# nrf51.net
KiCad netlist of a schematic drawn in Altium Designer
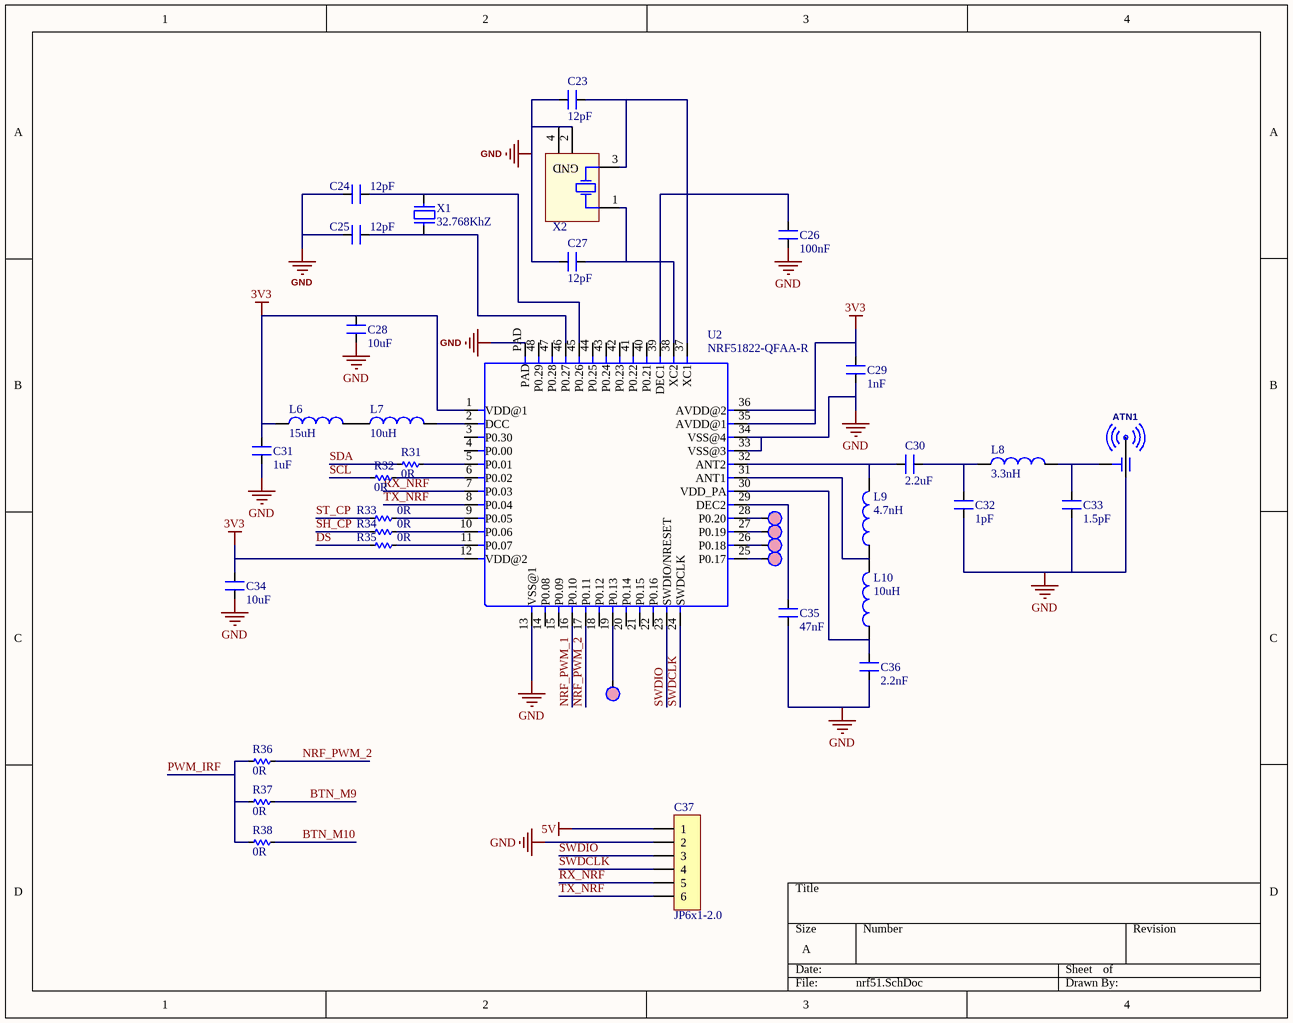
[diagram p0: nrf51.SchDoc]

(export (version "E")
  (design (tool "Eeschema 10.0.6"))
  (components
    (comp (ref "ATN1")
      (value "P-ANT")
      (footprint "Antenna 2G4")
      (libsource (lib "VitalSignal EcgPpg Board") (part "P-ANT"))
    )
    (comp (ref "C23")
      (value "12pF")
      (footprint "CN-SMD-0603")
      (description "Tu gom")
      (libsource (lib "LIBTanCN") (part "CN"))
    )
    (comp (ref "C24")
      (value "12pF")
      (footprint "CN-SMD-0603")
      (description "Tu gom")
      (libsource (lib "LIBTanCN") (part "CN"))
    )
    (comp (ref "C25")
      (value "12pF")
      (footprint "CN-SMD-0603")
      (description "Tu gom")
      (libsource (lib "LIBTanCN") (part "CN"))
    )
    (comp (ref "C26")
      (value "100nF")
      (footprint "CN-SMD-0603")
      (description "Tu gom")
      (libsource (lib "LIBTanCN") (part "CN"))
    )
    (comp (ref "C27")
      (value "12pF")
      (footprint "CN-SMD-0603")
      (description "Tu gom")
      (libsource (lib "LIBTanCN") (part "CN"))
    )
    (comp (ref "C28")
      (value "10uF")
      (footprint "CN-SMD-0603")
      (description "Tu gom")
      (libsource (lib "LIBTanCN") (part "CN"))
    )
    (comp (ref "C29")
      (value "1nF")
      (footprint "CN-SMD-0603")
      (description "Tu gom")
      (libsource (lib "LIBTanCN") (part "CN"))
    )
    (comp (ref "C30")
      (value "2.2uF")
      (footprint "CN-SMD-0603")
      (description "Tu gom")
      (libsource (lib "LIBTanCN") (part "CN"))
    )
    (comp (ref "C31")
      (value "1uF")
      (footprint "CN-SMD-0603")
      (description "Tu gom")
      (libsource (lib "LIBTanCN") (part "CN"))
    )
    (comp (ref "C32")
      (value "1pF")
      (footprint "CN-SMD-0603")
      (description "Tu gom")
      (libsource (lib "LIBTanCN") (part "CN"))
    )
    (comp (ref "C33")
      (value "1.5pF")
      (footprint "CN-SMD-0603")
      (description "Tu gom")
      (libsource (lib "LIBTanCN") (part "CN"))
    )
    (comp (ref "C34")
      (value "10uF")
      (footprint "CN-SMD-0603")
      (description "Tu gom")
      (libsource (lib "LIBTanCN") (part "CN"))
    )
    (comp (ref "C35")
      (value "47nF")
      (footprint "CN-SMD-0603")
      (description "Tu gom")
      (libsource (lib "LIBTanCN") (part "CN"))
    )
    (comp (ref "C36")
      (value "2.2nF")
      (footprint "CN-SMD-0603")
      (description "Tu gom")
      (libsource (lib "LIBTanCN") (part "CN"))
    )
    (comp (ref "C37")
      (value "JP6x1-2.0")
      (footprint "J6-C1T")
      (description "WR-PHD 2.00 mm Socket Header")
      (fields
        (field (name "MANUFACTURER") "Würth Elektronik eiSos GmbH")
        (field (name "PARTNO") "62000611821")
        (field (name "CREATED BY") "Karrer Zheng")
      )
      (libsource (lib "LIBRARY") (part "JP6x1-2.0"))
    )
    (comp (ref "L6")
      (value "15uH")
      (footprint "Inductor_0603:INDC1608X95N")
      (description "Ind Chip Shielded Multi-Layer 10uH 30% 1MHz Ferrite 50mA 0603 T/R")
      (fields (field (name "MP") "ASMCI-0603-100N-T"))
      (libsource (lib "Inductor_0603") (part "ASMCI-0603-100N-T"))
    )
    (comp (ref "L7")
      (value "10uH")
      (footprint "Inductor_0603:INDC1608X95N")
      (description "Ind Chip Shielded Multi-Layer 10uH 30% 1MHz Ferrite 50mA 0603 T/R")
      (fields (field (name "MP") "ASMCI-0603-100N-T"))
      (libsource (lib "Inductor_0603") (part "ASMCI-0603-100N-T"))
    )
    (comp (ref "L8")
      (value "3.3nH")
      (footprint "Inductor_0603:INDC1608X95N")
      (description "Ind Chip Shielded Multi-Layer 10uH 30% 1MHz Ferrite 50mA 0603 T/R")
      (fields (field (name "MP") "ASMCI-0603-100N-T"))
      (libsource (lib "Inductor_0603") (part "ASMCI-0603-100N-T"))
    )
    (comp (ref "L9")
      (value "4.7nH")
      (footprint "Inductor_0603:INDC1608X95N")
      (description "Ind Chip Shielded Multi-Layer 10uH 30% 1MHz Ferrite 50mA 0603 T/R")
      (fields (field (name "MP") "ASMCI-0603-100N-T"))
      (libsource (lib "Inductor_0603") (part "ASMCI-0603-100N-T"))
    )
    (comp (ref "L10")
      (value "10uH")
      (footprint "Inductor_0603:INDC1608X95N")
      (description "Ind Chip Shielded Multi-Layer 10uH 30% 1MHz Ferrite 50mA 0603 T/R")
      (fields (field (name "MP") "ASMCI-0603-100N-T"))
      (libsource (lib "Inductor_0603") (part "ASMCI-0603-100N-T"))
    )
    (comp (ref "R31")
      (value "0R")
      (footprint "RES-SMD-0603")
      (description "Resistor")
      (fields
        (field (name "MANUFACTURER") "Generic Components")
        (field (name "PUBLISHER") "Altium Hobart Technology Centre")
      )
      (libsource (lib "LIBRARY") (part "Res-SMD"))
    )
    (comp (ref "R32")
      (value "0R")
      (footprint "RES-SMD-0603")
      (description "Resistor")
      (fields
        (field (name "MANUFACTURER") "Generic Components")
        (field (name "PUBLISHER") "Altium Hobart Technology Centre")
      )
      (libsource (lib "LIBRARY") (part "Res-SMD"))
    )
    (comp (ref "R33")
      (value "0R")
      (footprint "RES-SMD-0603")
      (description "Resistor")
      (fields
        (field (name "MANUFACTURER") "Generic Components")
        (field (name "PUBLISHER") "Altium Hobart Technology Centre")
      )
      (libsource (lib "LIBRARY") (part "Res-SMD"))
    )
    (comp (ref "R34")
      (value "0R")
      (footprint "RES-SMD-0603")
      (description "Resistor")
      (fields
        (field (name "MANUFACTURER") "Generic Components")
        (field (name "PUBLISHER") "Altium Hobart Technology Centre")
      )
      (libsource (lib "LIBRARY") (part "Res-SMD"))
    )
    (comp (ref "R35")
      (value "0R")
      (footprint "RES-SMD-0603")
      (description "Resistor")
      (fields
        (field (name "MANUFACTURER") "Generic Components")
        (field (name "PUBLISHER") "Altium Hobart Technology Centre")
      )
      (libsource (lib "LIBRARY") (part "Res-SMD"))
    )
    (comp (ref "R36")
      (value "0R")
      (footprint "RES-SMD-0603")
      (description "Resistor")
      (fields
        (field (name "MANUFACTURER") "Generic Components")
        (field (name "PUBLISHER") "Altium Hobart Technology Centre")
      )
      (libsource (lib "LIBRARY") (part "Res-SMD"))
    )
    (comp (ref "R37")
      (value "0R")
      (footprint "RES-SMD-0603")
      (description "Resistor")
      (fields
        (field (name "MANUFACTURER") "Generic Components")
        (field (name "PUBLISHER") "Altium Hobart Technology Centre")
      )
      (libsource (lib "LIBRARY") (part "Res-SMD"))
    )
    (comp (ref "R38")
      (value "0R")
      (footprint "RES-SMD-0603")
      (description "Resistor")
      (fields
        (field (name "MANUFACTURER") "Generic Components")
        (field (name "PUBLISHER") "Altium Hobart Technology Centre")
      )
      (libsource (lib "LIBRARY") (part "Res-SMD"))
    )
    (comp (ref "TP1")
      (value "TP")
      (footprint "P-TP 1MM")
      (libsource (lib "VitalSignal EcgPpg Board") (part "P-TESTPOINT"))
    )
    (comp (ref "TP2")
      (value "TP")
      (footprint "P-TP 1MM")
      (libsource (lib "VitalSignal EcgPpg Board") (part "P-TESTPOINT"))
    )
    (comp (ref "TP3")
      (value "TP")
      (footprint "P-TP 1MM")
      (libsource (lib "VitalSignal EcgPpg Board") (part "P-TESTPOINT"))
    )
    (comp (ref "TP4")
      (value "TP")
      (footprint "P-TP 1MM")
      (libsource (lib "VitalSignal EcgPpg Board") (part "P-TESTPOINT"))
    )
    (comp (ref "TP5")
      (value "TP")
      (footprint "P-TP 1MM")
      (libsource (lib "VitalSignal EcgPpg Board") (part "P-TESTPOINT"))
    )
    (comp (ref "U2")
      (value "NRF51822-QFAA-R")
      (footprint "QFN48G-0.4-6X6MM:QFN48G-0.4-6X6MM")
      (description "IC RF TxRx + MCU Bluetooth, General ISM > 1GHz Bluetooth v4.0 2.4GHz 48-VFQFN Exposed Pad")
      (fields (field (name "MF") "Nordic"))
      (libsource (lib "NRF51822-QFAA-R") (part "NRF51822-QFAA-R"))
    )
    (comp (ref "X1")
      (value "32.768KhZ")
      (footprint "XT2-32.768KHz-2_V")
      (description "Crystal, 32.768 KHz, -40 to 85 degC, 3.2 x 1.5 x 0.9 mm SMD")
      (libsource (lib "LIBRARY") (part "XT2"))
    )
    (comp (ref "X2")
      (value "XT4")
      (footprint "XT4-16.000MHz-4_V")
      (description "Crystal, 16 MHz, -30 to 85 degC, 3.2 x 2.5 x 0.9 mm SMD")
      (libsource (lib "LIBRARY") (part "XT4"))
    )
  )
  (nets
    (net (code "1") (name "/BTN_M9") (class "Default")
      (node (ref "R37") (pin "1") (pinfunction "1_1") (pintype "passive"))
    )
    (net (code "2") (name "/BTN_M10") (class "Default")
      (node (ref "R38") (pin "1") (pinfunction "1_1") (pintype "passive"))
    )
    (net (code "3") (name "/DS") (class "Default")
      (node (ref "R35") (pin "1") (pinfunction "1_1") (pintype "passive"))
    )
    (net (code "4") (name "/NRF_PWM_1") (class "Default")
      (node (ref "U2") (pin "16") (pinfunction "P0.10_16") (pintype "bidirectional"))
    )
    (net (code "5") (name "/NRF_PWM_2") (class "Default")
      (node (ref "R36") (pin "1") (pinfunction "1_1") (pintype "passive"))
      (node (ref "U2") (pin "17") (pinfunction "P0.11_17") (pintype "bidirectional"))
    )
    (net (code "6") (name "/PWM_IRF") (class "Default")
      (node (ref "R36") (pin "2") (pinfunction "2_2") (pintype "passive"))
      (node (ref "R37") (pin "2") (pinfunction "2_2") (pintype "passive"))
      (node (ref "R38") (pin "2") (pinfunction "2_2") (pintype "passive"))
    )
    (net (code "7") (name "/RX_NRF") (class "Default")
      (node (ref "C37") (pin "5") (pinfunction "5_5") (pintype "passive"))
      (node (ref "U2") (pin "7") (pinfunction "P0.03_7") (pintype "bidirectional"))
    )
    (net (code "8") (name "/SCL") (class "Default")
      (node (ref "R32") (pin "2") (pinfunction "2_2") (pintype "passive"))
    )
    (net (code "9") (name "/SDA") (class "Default")
      (node (ref "R31") (pin "2") (pinfunction "2_2") (pintype "passive"))
    )
    (net (code "10") (name "/SH_CP") (class "Default")
      (node (ref "R34") (pin "1") (pinfunction "1_1") (pintype "passive"))
    )
    (net (code "11") (name "/ST_CP") (class "Default")
      (node (ref "R33") (pin "1") (pinfunction "1_1") (pintype "passive"))
    )
    (net (code "12") (name "/SWDCLK") (class "Default")
      (node (ref "C37") (pin "4") (pinfunction "4_4") (pintype "passive"))
      (node (ref "U2") (pin "24") (pinfunction "SWDCLK_24") (pintype "bidirectional"))
    )
    (net (code "13") (name "/SWDIO") (class "Default")
      (node (ref "C37") (pin "3") (pinfunction "3_3") (pintype "passive"))
      (node (ref "U2") (pin "23") (pinfunction "SWDIO/NRESET_23") (pintype "bidirectional"))
    )
    (net (code "14") (name "/TX_NRF") (class "Default")
      (node (ref "C37") (pin "6") (pinfunction "6_6") (pintype "passive"))
      (node (ref "U2") (pin "8") (pinfunction "P0.04_8") (pintype "bidirectional"))
    )
    (net (code "15") (name "3V3") (class "Default")
      (node (ref "C28") (pin "1") (pinfunction "1_1") (pintype "passive"))
      (node (ref "C29") (pin "2") (pinfunction "2_2") (pintype "passive"))
      (node (ref "C31") (pin "1") (pinfunction "1_1") (pintype "passive"))
      (node (ref "C34") (pin "1") (pinfunction "1_1") (pintype "passive"))
      (node (ref "L6") (pin "1") (pinfunction "1_1") (pintype "passive"))
      (node (ref "U2") (pin "1") (pinfunction "VDD@1_1") (pintype "bidirectional"))
      (node (ref "U2") (pin "12") (pinfunction "VDD@2_12") (pintype "bidirectional"))
      (node (ref "U2") (pin "35") (pinfunction "AVDD@1_35") (pintype "bidirectional"))
      (node (ref "U2") (pin "36") (pinfunction "AVDD@2_36") (pintype "bidirectional"))
    )
    (net (code "16") (name "5V") (class "Default")
      (node (ref "C37") (pin "1") (pinfunction "1_1") (pintype "passive"))
    )
    (net (code "17") (name "GND") (class "Default")
      (node (ref "ATN1") (pin "1") (pinfunction "1_1") (pintype "passive"))
      (node (ref "C23") (pin "1") (pinfunction "1_1") (pintype "passive"))
      (node (ref "C24") (pin "2") (pinfunction "2_2") (pintype "passive"))
      (node (ref "C25") (pin "2") (pinfunction "2_2") (pintype "passive"))
      (node (ref "C26") (pin "2") (pinfunction "2_2") (pintype "passive"))
      (node (ref "C27") (pin "1") (pinfunction "1_1") (pintype "passive"))
      (node (ref "C28") (pin "2") (pinfunction "2_2") (pintype "passive"))
      (node (ref "C29") (pin "1") (pinfunction "1_1") (pintype "passive"))
      (node (ref "C31") (pin "2") (pinfunction "2_2") (pintype "passive"))
      (node (ref "C32") (pin "2") (pinfunction "2_2") (pintype "passive"))
      (node (ref "C33") (pin "2") (pinfunction "2_2") (pintype "passive"))
      (node (ref "C34") (pin "2") (pinfunction "2_2") (pintype "passive"))
      (node (ref "C35") (pin "2") (pinfunction "2_2") (pintype "passive"))
      (node (ref "C36") (pin "2") (pinfunction "2_2") (pintype "passive"))
      (node (ref "C37") (pin "2") (pinfunction "2_2") (pintype "passive"))
      (node (ref "U2") (pin "13") (pinfunction "VSS@1_13") (pintype "bidirectional"))
      (node (ref "U2") (pin "33") (pinfunction "VSS@3_33") (pintype "bidirectional"))
      (node (ref "U2") (pin "34") (pinfunction "VSS@4_34") (pintype "bidirectional"))
      (node (ref "U2") (pin "PAD") (pinfunction "PAD_PAD") (pintype "bidirectional"))
      (node (ref "X2") (pin "2") (pinfunction "GND_2") (pintype "power_in"))
      (node (ref "X2") (pin "4") (pinfunction "GND_4") (pintype "power_in"))
    )
    (net (code "18") (name "Net-(ATN1-Pad2)") (class "Default")
      (node (ref "ATN1") (pin "2") (pinfunction "2_2") (pintype "passive"))
      (node (ref "C33") (pin "1") (pinfunction "1_1") (pintype "passive"))
      (node (ref "L8") (pin "2") (pinfunction "2_2") (pintype "passive"))
    )
    (net (code "19") (name "Net-(C30-Pad1)") (class "Default")
      (node (ref "C30") (pin "1") (pinfunction "1_1") (pintype "passive"))
      (node (ref "C32") (pin "1") (pinfunction "1_1") (pintype "passive"))
      (node (ref "L8") (pin "1") (pinfunction "1_1") (pintype "passive"))
    )
    (net (code "20") (name "Net-(L6-Pad2)") (class "Default")
      (node (ref "L6") (pin "2") (pinfunction "2_2") (pintype "passive"))
      (node (ref "L7") (pin "1") (pinfunction "1_1") (pintype "passive"))
    )
    (net (code "21") (name "Net-(U2-ANT1)") (class "Default")
      (node (ref "L10") (pin "2") (pinfunction "2_2") (pintype "passive"))
      (node (ref "L9") (pin "1") (pinfunction "1_1") (pintype "passive"))
      (node (ref "U2") (pin "31") (pinfunction "ANT1_31") (pintype "bidirectional"))
    )
    (net (code "22") (name "Net-(U2-ANT2)") (class "Default")
      (node (ref "C30") (pin "2") (pinfunction "2_2") (pintype "passive"))
      (node (ref "L9") (pin "2") (pinfunction "2_2") (pintype "passive"))
      (node (ref "U2") (pin "32") (pinfunction "ANT2_32") (pintype "bidirectional"))
    )
    (net (code "23") (name "Net-(U2-DCC)") (class "Default")
      (node (ref "L7") (pin "2") (pinfunction "2_2") (pintype "passive"))
      (node (ref "U2") (pin "2") (pinfunction "DCC_2") (pintype "bidirectional"))
    )
    (net (code "24") (name "Net-(U2-DEC1)") (class "Default")
      (node (ref "C26") (pin "1") (pinfunction "1_1") (pintype "passive"))
      (node (ref "U2") (pin "39") (pinfunction "DEC1_39") (pintype "bidirectional"))
    )
    (net (code "25") (name "Net-(U2-DEC2)") (class "Default")
      (node (ref "C35") (pin "1") (pinfunction "1_1") (pintype "passive"))
      (node (ref "U2") (pin "29") (pinfunction "DEC2_29") (pintype "bidirectional"))
    )
    (net (code "26") (name "Net-(U2-P0.01)") (class "Default")
      (node (ref "R31") (pin "1") (pinfunction "1_1") (pintype "passive"))
      (node (ref "U2") (pin "5") (pinfunction "P0.01_5") (pintype "bidirectional"))
    )
    (net (code "27") (name "Net-(U2-P0.02)") (class "Default")
      (node (ref "R32") (pin "1") (pinfunction "1_1") (pintype "passive"))
      (node (ref "U2") (pin "6") (pinfunction "P0.02_6") (pintype "bidirectional"))
    )
    (net (code "28") (name "Net-(U2-P0.05)") (class "Default")
      (node (ref "R33") (pin "2") (pinfunction "2_2") (pintype "passive"))
      (node (ref "U2") (pin "9") (pinfunction "P0.05_9") (pintype "bidirectional"))
    )
    (net (code "29") (name "Net-(U2-P0.06)") (class "Default")
      (node (ref "R34") (pin "2") (pinfunction "2_2") (pintype "passive"))
      (node (ref "U2") (pin "10") (pinfunction "P0.06_10") (pintype "bidirectional"))
    )
    (net (code "30") (name "Net-(U2-P0.07)") (class "Default")
      (node (ref "R35") (pin "2") (pinfunction "2_2") (pintype "passive"))
      (node (ref "U2") (pin "11") (pinfunction "P0.07_11") (pintype "bidirectional"))
    )
    (net (code "31") (name "Net-(U2-P0.13)") (class "Default")
      (node (ref "TP5") (pin "1") (pinfunction "1_1") (pintype "passive"))
      (node (ref "U2") (pin "19") (pinfunction "P0.13_19") (pintype "bidirectional"))
    )
    (net (code "32") (name "Net-(U2-P0.17)") (class "Default")
      (node (ref "TP4") (pin "1") (pinfunction "1_1") (pintype "passive"))
      (node (ref "U2") (pin "25") (pinfunction "P0.17_25") (pintype "bidirectional"))
    )
    (net (code "33") (name "Net-(U2-P0.18)") (class "Default")
      (node (ref "TP3") (pin "1") (pinfunction "1_1") (pintype "passive"))
      (node (ref "U2") (pin "26") (pinfunction "P0.18_26") (pintype "bidirectional"))
    )
    (net (code "34") (name "Net-(U2-P0.19)") (class "Default")
      (node (ref "TP2") (pin "1") (pinfunction "1_1") (pintype "passive"))
      (node (ref "U2") (pin "27") (pinfunction "P0.19_27") (pintype "bidirectional"))
    )
    (net (code "35") (name "Net-(U2-P0.20)") (class "Default")
      (node (ref "TP1") (pin "1") (pinfunction "1_1") (pintype "passive"))
      (node (ref "U2") (pin "28") (pinfunction "P0.20_28") (pintype "bidirectional"))
    )
    (net (code "36") (name "Net-(U2-P0.26)") (class "Default")
      (node (ref "C24") (pin "1") (pinfunction "1_1") (pintype "passive"))
      (node (ref "U2") (pin "45") (pinfunction "P0.26_45") (pintype "bidirectional"))
      (node (ref "X1") (pin "2") (pinfunction "2_2") (pintype "passive"))
    )
    (net (code "37") (name "Net-(U2-P0.27)") (class "Default")
      (node (ref "C25") (pin "1") (pinfunction "1_1") (pintype "passive"))
      (node (ref "U2") (pin "46") (pinfunction "P0.27_46") (pintype "bidirectional"))
      (node (ref "X1") (pin "1") (pinfunction "1_1") (pintype "passive"))
    )
    (net (code "38") (name "Net-(U2-VDD_PA)") (class "Default")
      (node (ref "C36") (pin "1") (pinfunction "1_1") (pintype "passive"))
      (node (ref "L10") (pin "1") (pinfunction "1_1") (pintype "passive"))
      (node (ref "U2") (pin "30") (pinfunction "VDD_PA_30") (pintype "bidirectional"))
    )
    (net (code "39") (name "Net-(U2-XC1)") (class "Default")
      (node (ref "C23") (pin "2") (pinfunction "2_2") (pintype "passive"))
      (node (ref "U2") (pin "37") (pinfunction "XC1_37") (pintype "bidirectional"))
      (node (ref "X2") (pin "3") (pinfunction "XTAL_3") (pintype "passive"))
    )
    (net (code "40") (name "Net-(U2-XC2)") (class "Default")
      (node (ref "C27") (pin "2") (pinfunction "2_2") (pintype "passive"))
      (node (ref "U2") (pin "38") (pinfunction "XC2_38") (pintype "bidirectional"))
      (node (ref "X2") (pin "1") (pinfunction "XTAL_1") (pintype "passive"))
    )
    (net (code "41") (name "unconnected-(U2-P0.00-Pad4)") (class "Default")
      (node (ref "U2") (pin "4") (pinfunction "P0.00_4") (pintype "bidirectional"))
    )
    (net (code "42") (name "unconnected-(U2-P0.08-Pad14)") (class "Default")
      (node (ref "U2") (pin "14") (pinfunction "P0.08_14") (pintype "bidirectional"))
    )
    (net (code "43") (name "unconnected-(U2-P0.09-Pad15)") (class "Default")
      (node (ref "U2") (pin "15") (pinfunction "P0.09_15") (pintype "bidirectional"))
    )
    (net (code "44") (name "unconnected-(U2-P0.12-Pad18)") (class "Default")
      (node (ref "U2") (pin "18") (pinfunction "P0.12_18") (pintype "bidirectional"))
    )
    (net (code "45") (name "unconnected-(U2-P0.14-Pad20)") (class "Default")
      (node (ref "U2") (pin "20") (pinfunction "P0.14_20") (pintype "bidirectional"))
    )
    (net (code "46") (name "unconnected-(U2-P0.15-Pad21)") (class "Default")
      (node (ref "U2") (pin "21") (pinfunction "P0.15_21") (pintype "bidirectional"))
    )
    (net (code "47") (name "unconnected-(U2-P0.16-Pad22)") (class "Default")
      (node (ref "U2") (pin "22") (pinfunction "P0.16_22") (pintype "bidirectional"))
    )
    (net (code "48") (name "unconnected-(U2-P0.21-Pad40)") (class "Default")
      (node (ref "U2") (pin "40") (pinfunction "P0.21_40") (pintype "bidirectional"))
    )
    (net (code "49") (name "unconnected-(U2-P0.22-Pad41)") (class "Default")
      (node (ref "U2") (pin "41") (pinfunction "P0.22_41") (pintype "bidirectional"))
    )
    (net (code "50") (name "unconnected-(U2-P0.23-Pad42)") (class "Default")
      (node (ref "U2") (pin "42") (pinfunction "P0.23_42") (pintype "bidirectional"))
    )
    (net (code "51") (name "unconnected-(U2-P0.24-Pad43)") (class "Default")
      (node (ref "U2") (pin "43") (pinfunction "P0.24_43") (pintype "bidirectional"))
    )
    (net (code "52") (name "unconnected-(U2-P0.25-Pad44)") (class "Default")
      (node (ref "U2") (pin "44") (pinfunction "P0.25_44") (pintype "bidirectional"))
    )
    (net (code "53") (name "unconnected-(U2-P0.28-Pad47)") (class "Default")
      (node (ref "U2") (pin "47") (pinfunction "P0.28_47") (pintype "bidirectional"))
    )
    (net (code "54") (name "unconnected-(U2-P0.29-Pad48)") (class "Default")
      (node (ref "U2") (pin "48") (pinfunction "P0.29_48") (pintype "bidirectional"))
    )
    (net (code "55") (name "unconnected-(U2-P0.30-Pad3)") (class "Default")
      (node (ref "U2") (pin "3") (pinfunction "P0.30_3") (pintype "bidirectional"))
    )
  )
)
